# attiny-bikelight.net
KiCad netlist of a schematic drawn in EAGLE
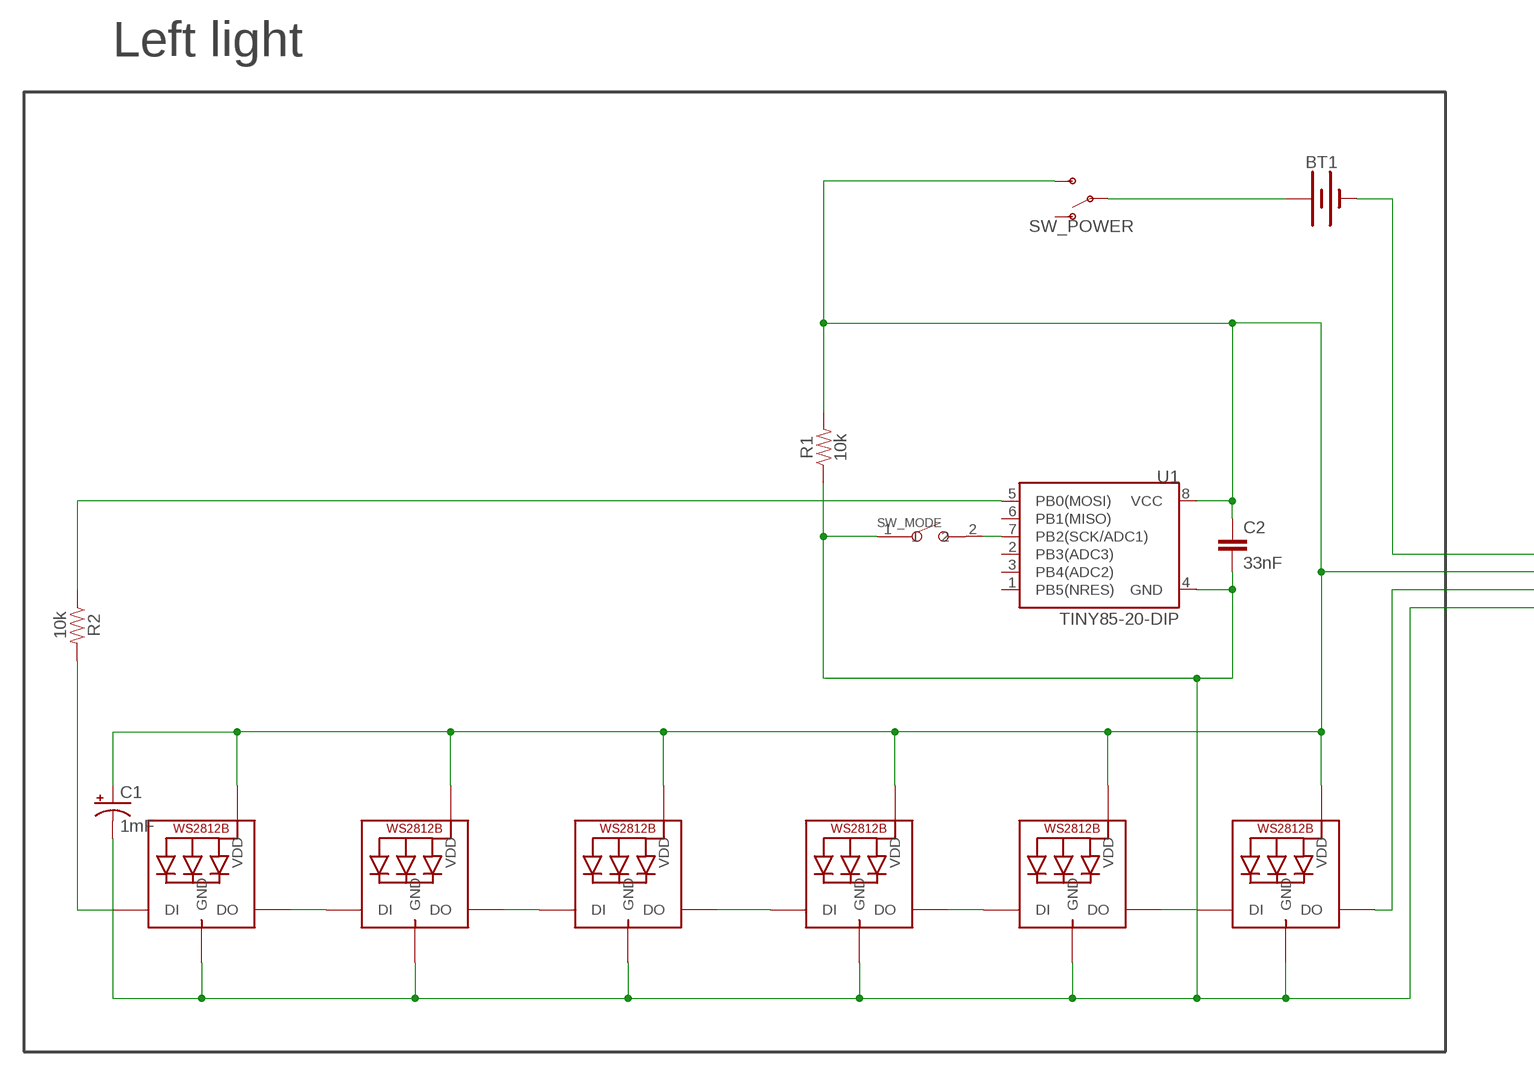
[diagram p0: schematic, sheet 1, part 1 of 2]
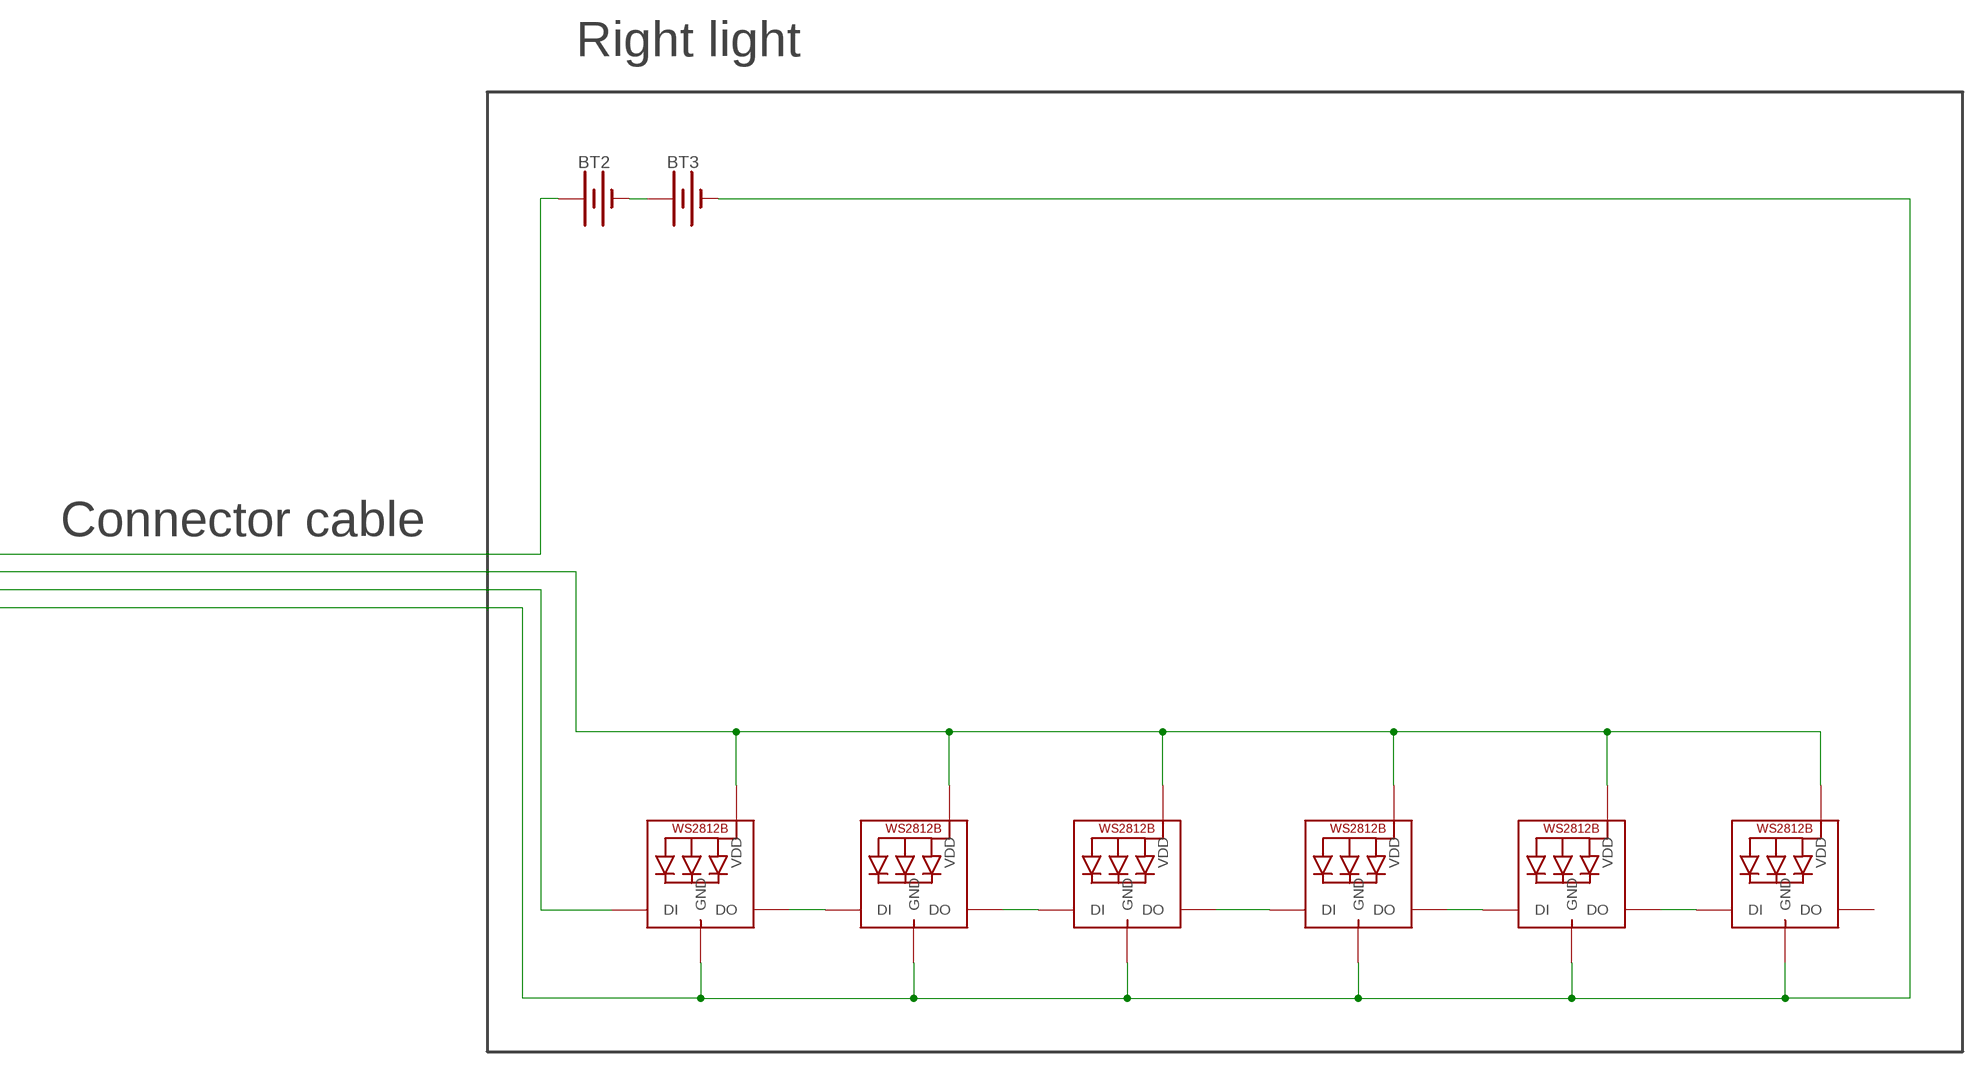
[diagram p1: schematic, sheet 1, part 2 of 2]

(export (version "E")
  (design (tool "Eeschema 10.0.6"))
  (components
    (comp (ref "BT1")
      (value "BATTERY-AAA")
      (footprint "eagle-import:BATTERY-AAA")
      (libsource (lib "eagle-import") (part "BATTERY-AAA"))
    )
    (comp (ref "BT2")
      (value "BATTERY-AAA")
      (footprint "eagle-import:BATTERY-AAA")
      (libsource (lib "eagle-import") (part "BATTERY-AAA"))
    )
    (comp (ref "BT3")
      (value "BATTERY-AAA")
      (footprint "eagle-import:BATTERY-AAA")
      (libsource (lib "eagle-import") (part "BATTERY-AAA"))
    )
    (comp (ref "C1")
      (value "1mF")
      (footprint "eagle-import:CPOL-RADIAL-5MM-10MM")
      (libsource (lib "eagle-import") (part "1000UF-RADIAL-5MM-25V-20%"))
    )
    (comp (ref "C2")
      (value "33nF")
      (footprint "eagle-import:0603")
      (libsource (lib "eagle-import") (part "33NF-0603-50V-10%"))
    )
    (comp (ref "LED1")
      (value "WS2812B5050")
      (footprint "eagle-import:WS2812B")
      (libsource (lib "eagle-import") (part "WS2812B5050"))
    )
    (comp (ref "LED2")
      (value "WS2812B5050")
      (footprint "eagle-import:WS2812B")
      (libsource (lib "eagle-import") (part "WS2812B5050"))
    )
    (comp (ref "LED3")
      (value "WS2812B5050")
      (footprint "eagle-import:WS2812B")
      (libsource (lib "eagle-import") (part "WS2812B5050"))
    )
    (comp (ref "LED4")
      (value "WS2812B5050")
      (footprint "eagle-import:WS2812B")
      (libsource (lib "eagle-import") (part "WS2812B5050"))
    )
    (comp (ref "LED5")
      (value "WS2812B5050")
      (footprint "eagle-import:WS2812B")
      (libsource (lib "eagle-import") (part "WS2812B5050"))
    )
    (comp (ref "LED6")
      (value "WS2812B5050")
      (footprint "eagle-import:WS2812B")
      (libsource (lib "eagle-import") (part "WS2812B5050"))
    )
    (comp (ref "LED7")
      (value "WS2812B5050")
      (footprint "eagle-import:WS2812B")
      (libsource (lib "eagle-import") (part "WS2812B5050"))
    )
    (comp (ref "LED8")
      (value "WS2812B5050")
      (footprint "eagle-import:WS2812B")
      (libsource (lib "eagle-import") (part "WS2812B5050"))
    )
    (comp (ref "LED9")
      (value "WS2812B5050")
      (footprint "eagle-import:WS2812B")
      (libsource (lib "eagle-import") (part "WS2812B5050"))
    )
    (comp (ref "LED10")
      (value "WS2812B5050")
      (footprint "eagle-import:WS2812B")
      (libsource (lib "eagle-import") (part "WS2812B5050"))
    )
    (comp (ref "LED11")
      (value "WS2812B5050")
      (footprint "eagle-import:WS2812B")
      (libsource (lib "eagle-import") (part "WS2812B5050"))
    )
    (comp (ref "LED12")
      (value "WS2812B5050")
      (footprint "eagle-import:WS2812B")
      (libsource (lib "eagle-import") (part "WS2812B5050"))
    )
    (comp (ref "R1")
      (value "10k")
      (footprint "eagle-import:AXIAL-0.1")
      (libsource (lib "eagle-import") (part "10KOHM-VERT-1/4W-1%"))
    )
    (comp (ref "R2")
      (value "10k")
      (footprint "eagle-import:AXIAL-0.1")
      (libsource (lib "eagle-import") (part "10KOHM-VERT-1/4W-1%"))
    )
    (comp (ref "SW_MODE")
      (value "DIP-BUTTON(2P-6.0X3.0X4.3MM)-TS-1101F")
      (footprint "eagle-import:SW2-5.0-6.0X3.0X4.3MM")
      (fields (field (name "MPN") "TS-1101F"))
      (libsource (lib "eagle-import") (part "DIP-BUTTON(2P-6.0X3.0X4.3MM)-TS-1101F"))
    )
    (comp (ref "SW_POWER")
      (value "SWITCH-SPDT-PTH-11.6X4.0MM-LOCK")
      (footprint "eagle-import:SWITCH_SPDT_PTH_11.6X4.0MM_LOCK")
      (libsource (lib "eagle-import") (part "SWITCH-SPDT-PTH-11.6X4.0MM-LOCK"))
    )
    (comp (ref "U1")
      (value "TINY85-20-DIP")
      (footprint "eagle-import:DIP08_MCU")
      (libsource (lib "eagle-import") (part "ATTINY45TINY85-20-DIP"))
    )
  )
  (nets
    (net (code "1") (name "Net-(BT1-+)") (class "Default")
      (node (ref "BT1") (pin "PWR@1") (pinfunction "+_PWR@1") (pintype "power_in"))
      (node (ref "SW_POWER") (pin "2") (pinfunction "P_2") (pintype "passive"))
    )
    (net (code "2") (name "Net-(BT1--)") (class "Default")
      (node (ref "BT1") (pin "GND@1") (pinfunction "-_GND@1") (pintype "power_in"))
      (node (ref "BT2") (pin "PWR@1") (pinfunction "+_PWR@1") (pintype "power_in"))
    )
    (net (code "3") (name "Net-(BT2--)") (class "Default")
      (node (ref "BT2") (pin "GND@1") (pinfunction "-_GND@1") (pintype "power_in"))
      (node (ref "BT3") (pin "PWR@1") (pinfunction "+_PWR@1") (pintype "power_in"))
    )
    (net (code "4") (name "Net-(BT3--)") (class "Default")
      (node (ref "BT3") (pin "GND@1") (pinfunction "-_GND@1") (pintype "power_in"))
      (node (ref "C1") (pin "-") (pinfunction "-_-") (pintype "passive"))
      (node (ref "C2") (pin "2") (pinfunction "2_2") (pintype "passive"))
      (node (ref "LED1") (pin "3-GND") (pinfunction "GND_3-GND") (pintype "power_in"))
      (node (ref "LED10") (pin "3-GND") (pinfunction "GND_3-GND") (pintype "power_in"))
      (node (ref "LED11") (pin "3-GND") (pinfunction "GND_3-GND") (pintype "power_in"))
      (node (ref "LED12") (pin "3-GND") (pinfunction "GND_3-GND") (pintype "power_in"))
      (node (ref "LED2") (pin "3-GND") (pinfunction "GND_3-GND") (pintype "power_in"))
      (node (ref "LED3") (pin "3-GND") (pinfunction "GND_3-GND") (pintype "power_in"))
      (node (ref "LED4") (pin "3-GND") (pinfunction "GND_3-GND") (pintype "power_in"))
      (node (ref "LED5") (pin "3-GND") (pinfunction "GND_3-GND") (pintype "power_in"))
      (node (ref "LED6") (pin "3-GND") (pinfunction "GND_3-GND") (pintype "power_in"))
      (node (ref "LED7") (pin "3-GND") (pinfunction "GND_3-GND") (pintype "power_in"))
      (node (ref "LED8") (pin "3-GND") (pinfunction "GND_3-GND") (pintype "power_in"))
      (node (ref "LED9") (pin "3-GND") (pinfunction "GND_3-GND") (pintype "power_in"))
      (node (ref "R1") (pin "P$1") (pinfunction "1_P$1") (pintype "passive"))
      (node (ref "SW_MODE") (pin "1") (pinfunction "1_1") (pintype "bidirectional"))
      (node (ref "U1") (pin "4") (pinfunction "GND_4") (pintype "bidirectional"))
    )
    (net (code "5") (name "Net-(LED1-DI)") (class "Default")
      (node (ref "LED1") (pin "4-DIN") (pinfunction "DI_4-DIN") (pintype "input"))
      (node (ref "LED2") (pin "2-DOUT") (pinfunction "DO_2-DOUT") (pintype "output"))
    )
    (net (code "6") (name "Net-(LED1-DO)") (class "Default")
      (node (ref "LED1") (pin "2-DOUT") (pinfunction "DO_2-DOUT") (pintype "output"))
      (node (ref "LED12") (pin "4-DIN") (pinfunction "DI_4-DIN") (pintype "input"))
    )
    (net (code "7") (name "Net-(LED1-VDD)") (class "Default")
      (node (ref "C1") (pin "+") (pinfunction "+_+") (pintype "passive"))
      (node (ref "C2") (pin "1") (pinfunction "1_1") (pintype "passive"))
      (node (ref "LED1") (pin "1-VDD") (pinfunction "VDD_1-VDD") (pintype "power_in"))
      (node (ref "LED10") (pin "1-VDD") (pinfunction "VDD_1-VDD") (pintype "power_in"))
      (node (ref "LED11") (pin "1-VDD") (pinfunction "VDD_1-VDD") (pintype "power_in"))
      (node (ref "LED12") (pin "1-VDD") (pinfunction "VDD_1-VDD") (pintype "power_in"))
      (node (ref "LED2") (pin "1-VDD") (pinfunction "VDD_1-VDD") (pintype "power_in"))
      (node (ref "LED3") (pin "1-VDD") (pinfunction "VDD_1-VDD") (pintype "power_in"))
      (node (ref "LED4") (pin "1-VDD") (pinfunction "VDD_1-VDD") (pintype "power_in"))
      (node (ref "LED5") (pin "1-VDD") (pinfunction "VDD_1-VDD") (pintype "power_in"))
      (node (ref "LED6") (pin "1-VDD") (pinfunction "VDD_1-VDD") (pintype "power_in"))
      (node (ref "LED7") (pin "1-VDD") (pinfunction "VDD_1-VDD") (pintype "power_in"))
      (node (ref "LED8") (pin "1-VDD") (pinfunction "VDD_1-VDD") (pintype "power_in"))
      (node (ref "LED9") (pin "1-VDD") (pinfunction "VDD_1-VDD") (pintype "power_in"))
      (node (ref "R1") (pin "P$2") (pinfunction "2_P$2") (pintype "passive"))
      (node (ref "SW_POWER") (pin "3") (pinfunction "S_3") (pintype "passive"))
      (node (ref "U1") (pin "8") (pinfunction "VCC_8") (pintype "bidirectional"))
    )
    (net (code "8") (name "Net-(LED2-DI)") (class "Default")
      (node (ref "LED2") (pin "4-DIN") (pinfunction "DI_4-DIN") (pintype "input"))
      (node (ref "LED3") (pin "2-DOUT") (pinfunction "DO_2-DOUT") (pintype "output"))
    )
    (net (code "9") (name "Net-(LED3-DI)") (class "Default")
      (node (ref "LED3") (pin "4-DIN") (pinfunction "DI_4-DIN") (pintype "input"))
      (node (ref "LED4") (pin "2-DOUT") (pinfunction "DO_2-DOUT") (pintype "output"))
    )
    (net (code "10") (name "Net-(LED4-DI)") (class "Default")
      (node (ref "LED4") (pin "4-DIN") (pinfunction "DI_4-DIN") (pintype "input"))
      (node (ref "LED5") (pin "2-DOUT") (pinfunction "DO_2-DOUT") (pintype "output"))
    )
    (net (code "11") (name "Net-(LED5-DI)") (class "Default")
      (node (ref "LED5") (pin "4-DIN") (pinfunction "DI_4-DIN") (pintype "input"))
      (node (ref "LED6") (pin "2-DOUT") (pinfunction "DO_2-DOUT") (pintype "output"))
    )
    (net (code "12") (name "Net-(LED6-DI)") (class "Default")
      (node (ref "LED6") (pin "4-DIN") (pinfunction "DI_4-DIN") (pintype "input"))
      (node (ref "R2") (pin "P$2") (pinfunction "2_P$2") (pintype "passive"))
    )
    (net (code "13") (name "Net-(LED7-DI)") (class "Default")
      (node (ref "LED7") (pin "4-DIN") (pinfunction "DI_4-DIN") (pintype "input"))
      (node (ref "LED8") (pin "2-DOUT") (pinfunction "DO_2-DOUT") (pintype "output"))
    )
    (net (code "14") (name "Net-(LED8-DI)") (class "Default")
      (node (ref "LED8") (pin "4-DIN") (pinfunction "DI_4-DIN") (pintype "input"))
      (node (ref "LED9") (pin "2-DOUT") (pinfunction "DO_2-DOUT") (pintype "output"))
    )
    (net (code "15") (name "Net-(LED10-DI)") (class "Default")
      (node (ref "LED10") (pin "4-DIN") (pinfunction "DI_4-DIN") (pintype "input"))
      (node (ref "LED11") (pin "2-DOUT") (pinfunction "DO_2-DOUT") (pintype "output"))
    )
    (net (code "16") (name "Net-(LED10-DO)") (class "Default")
      (node (ref "LED10") (pin "2-DOUT") (pinfunction "DO_2-DOUT") (pintype "output"))
      (node (ref "LED9") (pin "4-DIN") (pinfunction "DI_4-DIN") (pintype "input"))
    )
    (net (code "17") (name "Net-(LED11-DI)") (class "Default")
      (node (ref "LED11") (pin "4-DIN") (pinfunction "DI_4-DIN") (pintype "input"))
      (node (ref "LED12") (pin "2-DOUT") (pinfunction "DO_2-DOUT") (pintype "output"))
    )
    (net (code "18") (name "Net-(R2-1)") (class "Default")
      (node (ref "R2") (pin "P$1") (pinfunction "1_P$1") (pintype "passive"))
      (node (ref "U1") (pin "5") (pinfunction "PB0(MOSI)_5") (pintype "bidirectional"))
    )
    (net (code "19") (name "Net-(U1-PB2(SCK{slash}ADC1))") (class "Default")
      (node (ref "SW_MODE") (pin "2") (pinfunction "2_2") (pintype "bidirectional"))
      (node (ref "U1") (pin "7") (pinfunction "PB2(SCK/ADC1)_7") (pintype "bidirectional"))
    )
    (net (code "20") (name "unconnected-(LED7-DO-Pad2-DOUT)") (class "Default")
      (node (ref "LED7") (pin "2-DOUT") (pinfunction "DO_2-DOUT") (pintype "output"))
    )
    (net (code "21") (name "unconnected-(SW_POWER-O-Pad1)") (class "Default")
      (node (ref "SW_POWER") (pin "1") (pinfunction "O_1") (pintype "passive"))
    )
    (net (code "22") (name "unconnected-(U1-PB1(MISO)-Pad6)") (class "Default")
      (node (ref "U1") (pin "6") (pinfunction "PB1(MISO)_6") (pintype "bidirectional"))
    )
    (net (code "23") (name "unconnected-(U1-PB3(ADC3)-Pad2)") (class "Default")
      (node (ref "U1") (pin "2") (pinfunction "PB3(ADC3)_2") (pintype "bidirectional"))
    )
    (net (code "24") (name "unconnected-(U1-PB4(ADC2)-Pad3)") (class "Default")
      (node (ref "U1") (pin "3") (pinfunction "PB4(ADC2)_3") (pintype "bidirectional"))
    )
    (net (code "25") (name "unconnected-(U1-PB5(NRES)-Pad1)") (class "Default")
      (node (ref "U1") (pin "1") (pinfunction "PB5(NRES)_1") (pintype "bidirectional"))
    )
  )
)
